# SoC_Decoupling.net
KiCad netlist of a schematic drawn in Altium Designer
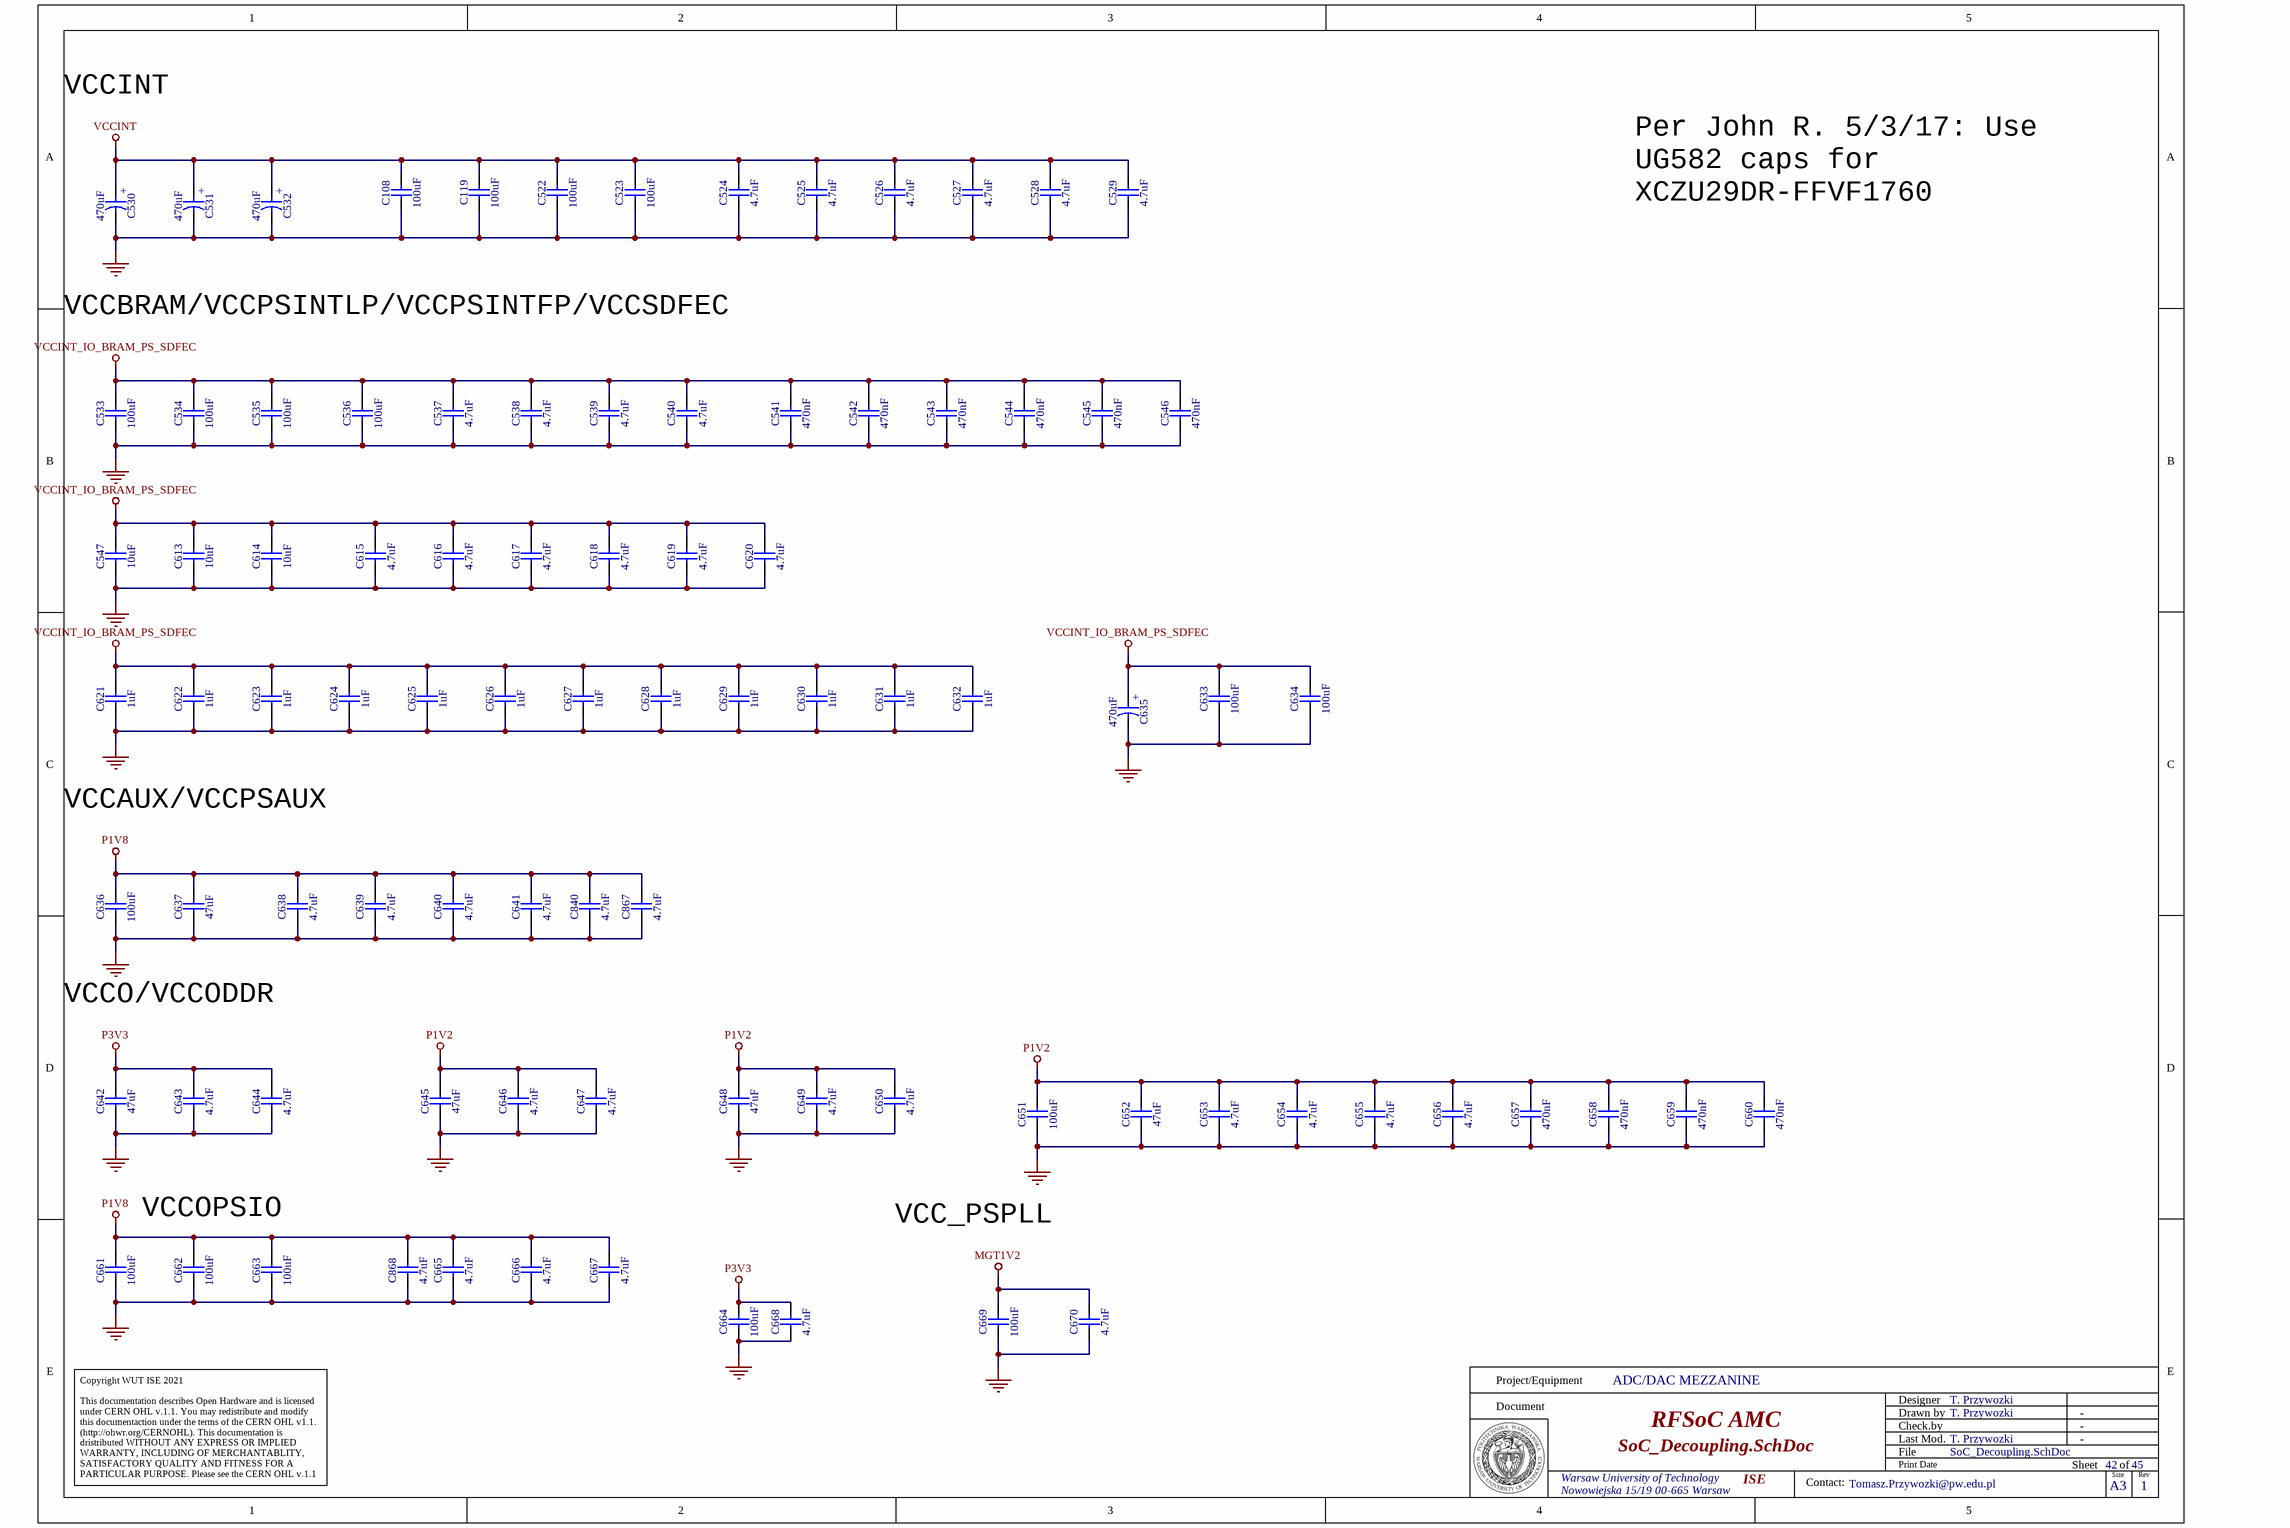
[diagram p0: SoC_Decoupling.SchDoc]

(export (version "E")
  (design (tool "Eeschema 10.0.6"))
  (components
    (comp (ref "C108")
      (value "100uF")
      (footprint "CAPC3216X180N")
      (description "Non-polarised capacitor")
      (fields
        (field (name "VOLTAGE") "6.3V")
        (field (name "TOLERANCE") "±10%")
        (field (name "AUTHOR") "CERN DEM JLC")
      )
      (libsource (lib "Capacitors") (part "Capacitor - non polarized"))
    )
    (comp (ref "C119")
      (value "100uF")
      (footprint "CAPC3216X180N")
      (description "Non-polarised capacitor")
      (fields
        (field (name "VOLTAGE") "6.3V")
        (field (name "TOLERANCE") "±10%")
        (field (name "AUTHOR") "CERN DEM JLC")
      )
      (libsource (lib "Capacitors") (part "Capacitor - non polarized"))
    )
    (comp (ref "C522")
      (value "100uF")
      (footprint "CAPC3216X180N")
      (description "Non-polarised capacitor")
      (fields
        (field (name "VOLTAGE") "6.3V")
        (field (name "TOLERANCE") "±10%")
        (field (name "AUTHOR") "CERN DEM JLC")
      )
      (libsource (lib "Capacitors") (part "Capacitor - non polarized"))
    )
    (comp (ref "C523")
      (value "100uF")
      (footprint "CAPC3216X180N")
      (description "Non-polarised capacitor")
      (fields
        (field (name "VOLTAGE") "6.3V")
        (field (name "TOLERANCE") "±10%")
        (field (name "AUTHOR") "CERN DEM JLC")
      )
      (libsource (lib "Capacitors") (part "Capacitor - non polarized"))
    )
    (comp (ref "C524")
      (value "4.7uF")
      (footprint "CAPC1005X55N")
      (description "Non-polarised capacitor")
      (fields
        (field (name "VOLTAGE") "6.3V")
        (field (name "TOLERANCE") "±20%")
        (field (name "AUTHOR") "CERN DEM JLC")
      )
      (libsource (lib "Capacitors") (part "Capacitor - non polarized"))
    )
    (comp (ref "C525")
      (value "4.7uF")
      (footprint "CAPC1005X55N")
      (description "Non-polarised capacitor")
      (fields
        (field (name "VOLTAGE") "6.3V")
        (field (name "TOLERANCE") "±20%")
        (field (name "AUTHOR") "CERN DEM JLC")
      )
      (libsource (lib "Capacitors") (part "Capacitor - non polarized"))
    )
    (comp (ref "C526")
      (value "4.7uF")
      (footprint "CAPC1005X55N")
      (description "Non-polarised capacitor")
      (fields
        (field (name "VOLTAGE") "6.3V")
        (field (name "TOLERANCE") "±20%")
        (field (name "AUTHOR") "CERN DEM JLC")
      )
      (libsource (lib "Capacitors") (part "Capacitor - non polarized"))
    )
    (comp (ref "C527")
      (value "4.7uF")
      (footprint "CAPC1005X55N")
      (description "Non-polarised capacitor")
      (fields
        (field (name "VOLTAGE") "6.3V")
        (field (name "TOLERANCE") "±20%")
        (field (name "AUTHOR") "CERN DEM JLC")
      )
      (libsource (lib "Capacitors") (part "Capacitor - non polarized"))
    )
    (comp (ref "C528")
      (value "4.7uF")
      (footprint "CAPC1005X55N")
      (description "Non-polarised capacitor")
      (fields
        (field (name "VOLTAGE") "6.3V")
        (field (name "TOLERANCE") "±20%")
        (field (name "AUTHOR") "CERN DEM JLC")
      )
      (libsource (lib "Capacitors") (part "Capacitor - non polarized"))
    )
    (comp (ref "C529")
      (value "4.7uF")
      (footprint "CAPC1005X55N")
      (description "Non-polarised capacitor")
      (fields
        (field (name "VOLTAGE") "6.3V")
        (field (name "TOLERANCE") "±20%")
        (field (name "AUTHOR") "CERN DEM JLC")
      )
      (libsource (lib "Capacitors") (part "Capacitor - non polarized"))
    )
    (comp (ref "C530")
      (value "470uF")
      (footprint "CAPMP7343X200N")
      (description "Polarised capacitor")
      (fields
        (field (name "VOLTAGE") "2V")
        (field (name "TOLERANCE") "±20%")
        (field (name "AUTHOR") "CERN DEM MR")
      )
      (libsource (lib "Capacitors") (part "Capacitor - polarized"))
    )
    (comp (ref "C531")
      (value "470uF")
      (footprint "CAPMP7343X200N")
      (description "Polarised capacitor")
      (fields
        (field (name "VOLTAGE") "2V")
        (field (name "TOLERANCE") "±20%")
        (field (name "AUTHOR") "CERN DEM MR")
      )
      (libsource (lib "Capacitors") (part "Capacitor - polarized"))
    )
    (comp (ref "C532")
      (value "470uF")
      (footprint "CAPMP7343X200N")
      (description "Polarised capacitor")
      (fields
        (field (name "VOLTAGE") "2V")
        (field (name "TOLERANCE") "±20%")
        (field (name "AUTHOR") "CERN DEM MR")
      )
      (libsource (lib "Capacitors") (part "Capacitor - polarized"))
    )
    (comp (ref "C533")
      (value "100uF")
      (footprint "CAPC3225X270N")
      (description "Non-polarised capacitor")
      (fields
        (field (name "VOLTAGE") "6.3V")
        (field (name "TOLERANCE") "±20%")
        (field (name "AUTHOR") "CERN DEM JLC")
      )
      (libsource (lib "Capacitors") (part "Capacitor - non polarized"))
    )
    (comp (ref "C534")
      (value "100uF")
      (footprint "CAPC3225X270N")
      (description "Non-polarised capacitor")
      (fields
        (field (name "VOLTAGE") "6.3V")
        (field (name "TOLERANCE") "±20%")
        (field (name "AUTHOR") "CERN DEM JLC")
      )
      (libsource (lib "Capacitors") (part "Capacitor - non polarized"))
    )
    (comp (ref "C535")
      (value "100uF")
      (footprint "CAPC3225X270N")
      (description "Non-polarised capacitor")
      (fields
        (field (name "VOLTAGE") "6.3V")
        (field (name "TOLERANCE") "±20%")
        (field (name "AUTHOR") "CERN DEM JLC")
      )
      (libsource (lib "Capacitors") (part "Capacitor - non polarized"))
    )
    (comp (ref "C536")
      (value "100uF")
      (footprint "CAPC3225X270N")
      (description "Non-polarised capacitor")
      (fields
        (field (name "VOLTAGE") "6.3V")
        (field (name "TOLERANCE") "±20%")
        (field (name "AUTHOR") "CERN DEM JLC")
      )
      (libsource (lib "Capacitors") (part "Capacitor - non polarized"))
    )
    (comp (ref "C537")
      (value "4.7uF")
      (footprint "CAPC1005X55N")
      (description "Non-polarised capacitor")
      (fields
        (field (name "VOLTAGE") "6.3V")
        (field (name "TOLERANCE") "±20%")
        (field (name "AUTHOR") "CERN DEM JLC")
      )
      (libsource (lib "Capacitors") (part "Capacitor - non polarized"))
    )
    (comp (ref "C538")
      (value "4.7uF")
      (footprint "CAPC1005X55N")
      (description "Non-polarised capacitor")
      (fields
        (field (name "VOLTAGE") "6.3V")
        (field (name "TOLERANCE") "±20%")
        (field (name "AUTHOR") "CERN DEM JLC")
      )
      (libsource (lib "Capacitors") (part "Capacitor - non polarized"))
    )
    (comp (ref "C539")
      (value "4.7uF")
      (footprint "CAPC1005X55N")
      (description "Non-polarised capacitor")
      (fields
        (field (name "VOLTAGE") "6.3V")
        (field (name "TOLERANCE") "±20%")
        (field (name "AUTHOR") "CERN DEM JLC")
      )
      (libsource (lib "Capacitors") (part "Capacitor - non polarized"))
    )
    (comp (ref "C540")
      (value "4.7uF")
      (footprint "CAPC1005X55N")
      (description "Non-polarised capacitor")
      (fields
        (field (name "VOLTAGE") "6.3V")
        (field (name "TOLERANCE") "±20%")
        (field (name "AUTHOR") "CERN DEM JLC")
      )
      (libsource (lib "Capacitors") (part "Capacitor - non polarized"))
    )
    (comp (ref "C541")
      (value "470nF")
      (footprint "CAPC1005X55N")
      (description "Non-polarised capacitor")
      (fields
        (field (name "VOLTAGE") "16V")
        (field (name "TOLERANCE") "±10%")
        (field (name "AUTHOR") "CERN DEM JLC")
      )
      (libsource (lib "Capacitors") (part "Capacitor - non polarized"))
    )
    (comp (ref "C542")
      (value "470nF")
      (footprint "CAPC1005X55N")
      (description "Non-polarised capacitor")
      (fields
        (field (name "VOLTAGE") "16V")
        (field (name "TOLERANCE") "±10%")
        (field (name "AUTHOR") "CERN DEM JLC")
      )
      (libsource (lib "Capacitors") (part "Capacitor - non polarized"))
    )
    (comp (ref "C543")
      (value "470nF")
      (footprint "CAPC1005X55N")
      (description "Non-polarised capacitor")
      (fields
        (field (name "VOLTAGE") "16V")
        (field (name "TOLERANCE") "±10%")
        (field (name "AUTHOR") "CERN DEM JLC")
      )
      (libsource (lib "Capacitors") (part "Capacitor - non polarized"))
    )
    (comp (ref "C544")
      (value "470nF")
      (footprint "CAPC1005X55N")
      (description "Non-polarised capacitor")
      (fields
        (field (name "VOLTAGE") "16V")
        (field (name "TOLERANCE") "±10%")
        (field (name "AUTHOR") "CERN DEM JLC")
      )
      (libsource (lib "Capacitors") (part "Capacitor - non polarized"))
    )
    (comp (ref "C545")
      (value "470nF")
      (footprint "CAPC1005X55N")
      (description "Non-polarised capacitor")
      (fields
        (field (name "VOLTAGE") "16V")
        (field (name "TOLERANCE") "±10%")
        (field (name "AUTHOR") "CERN DEM JLC")
      )
      (libsource (lib "Capacitors") (part "Capacitor - non polarized"))
    )
    (comp (ref "C546")
      (value "470nF")
      (footprint "CAPC1005X55N")
      (description "Non-polarised capacitor")
      (fields
        (field (name "VOLTAGE") "16V")
        (field (name "TOLERANCE") "±10%")
        (field (name "AUTHOR") "CERN DEM JLC")
      )
      (libsource (lib "Capacitors") (part "Capacitor - non polarized"))
    )
    (comp (ref "C547")
      (value "10uF")
      (footprint "CAPC1608X80N")
      (description "Non-polarised capacitor")
      (fields
        (field (name "VOLTAGE") "10V")
        (field (name "TOLERANCE") "±10%")
        (field (name "AUTHOR") "CERN DEM JLC")
      )
      (libsource (lib "Capacitors") (part "Capacitor - non polarized"))
    )
    (comp (ref "C613")
      (value "10uF")
      (footprint "CAPC1608X80N")
      (description "Non-polarised capacitor")
      (fields
        (field (name "VOLTAGE") "10V")
        (field (name "TOLERANCE") "±10%")
        (field (name "AUTHOR") "CERN DEM JLC")
      )
      (libsource (lib "Capacitors") (part "Capacitor - non polarized"))
    )
    (comp (ref "C614")
      (value "10uF")
      (footprint "CAPC1608X80N")
      (description "Non-polarised capacitor")
      (fields
        (field (name "VOLTAGE") "10V")
        (field (name "TOLERANCE") "±10%")
        (field (name "AUTHOR") "CERN DEM JLC")
      )
      (libsource (lib "Capacitors") (part "Capacitor - non polarized"))
    )
    (comp (ref "C615")
      (value "4.7uF")
      (footprint "CAPC1005X55N")
      (description "Non-polarised capacitor")
      (fields
        (field (name "VOLTAGE") "6.3V")
        (field (name "TOLERANCE") "±20%")
        (field (name "AUTHOR") "CERN DEM JLC")
      )
      (libsource (lib "Capacitors") (part "Capacitor - non polarized"))
    )
    (comp (ref "C616")
      (value "4.7uF")
      (footprint "CAPC1005X55N")
      (description "Non-polarised capacitor")
      (fields
        (field (name "VOLTAGE") "6.3V")
        (field (name "TOLERANCE") "±20%")
        (field (name "AUTHOR") "CERN DEM JLC")
      )
      (libsource (lib "Capacitors") (part "Capacitor - non polarized"))
    )
    (comp (ref "C617")
      (value "4.7uF")
      (footprint "CAPC1005X55N")
      (description "Non-polarised capacitor")
      (fields
        (field (name "VOLTAGE") "6.3V")
        (field (name "TOLERANCE") "±20%")
        (field (name "AUTHOR") "CERN DEM JLC")
      )
      (libsource (lib "Capacitors") (part "Capacitor - non polarized"))
    )
    (comp (ref "C618")
      (value "4.7uF")
      (footprint "CAPC1005X55N")
      (description "Non-polarised capacitor")
      (fields
        (field (name "VOLTAGE") "6.3V")
        (field (name "TOLERANCE") "±20%")
        (field (name "AUTHOR") "CERN DEM JLC")
      )
      (libsource (lib "Capacitors") (part "Capacitor - non polarized"))
    )
    (comp (ref "C619")
      (value "4.7uF")
      (footprint "CAPC1005X55N")
      (description "Non-polarised capacitor")
      (fields
        (field (name "VOLTAGE") "6.3V")
        (field (name "TOLERANCE") "±20%")
        (field (name "AUTHOR") "CERN DEM JLC")
      )
      (libsource (lib "Capacitors") (part "Capacitor - non polarized"))
    )
    (comp (ref "C620")
      (value "4.7uF")
      (footprint "CAPC1005X55N")
      (description "Non-polarised capacitor")
      (fields
        (field (name "VOLTAGE") "6.3V")
        (field (name "TOLERANCE") "±20%")
        (field (name "AUTHOR") "CERN DEM JLC")
      )
      (libsource (lib "Capacitors") (part "Capacitor - non polarized"))
    )
    (comp (ref "C621")
      (value "1uF")
      (footprint "CAPC1005X55N")
      (description "Non-polarised capacitor")
      (fields
        (field (name "VOLTAGE") "16V")
        (field (name "TOLERANCE") "±10%")
        (field (name "AUTHOR") "CERN DEM JLC")
      )
      (libsource (lib "Capacitors") (part "Capacitor - non polarized"))
    )
    (comp (ref "C622")
      (value "1uF")
      (footprint "CAPC1005X55N")
      (description "Non-polarised capacitor")
      (fields
        (field (name "VOLTAGE") "16V")
        (field (name "TOLERANCE") "±10%")
        (field (name "AUTHOR") "CERN DEM JLC")
      )
      (libsource (lib "Capacitors") (part "Capacitor - non polarized"))
    )
    (comp (ref "C623")
      (value "1uF")
      (footprint "CAPC1005X55N")
      (description "Non-polarised capacitor")
      (fields
        (field (name "VOLTAGE") "16V")
        (field (name "TOLERANCE") "±10%")
        (field (name "AUTHOR") "CERN DEM JLC")
      )
      (libsource (lib "Capacitors") (part "Capacitor - non polarized"))
    )
    (comp (ref "C624")
      (value "1uF")
      (footprint "CAPC1005X55N")
      (description "Non-polarised capacitor")
      (fields
        (field (name "VOLTAGE") "16V")
        (field (name "TOLERANCE") "±10%")
        (field (name "AUTHOR") "CERN DEM JLC")
      )
      (libsource (lib "Capacitors") (part "Capacitor - non polarized"))
    )
    (comp (ref "C625")
      (value "1uF")
      (footprint "CAPC1005X55N")
      (description "Non-polarised capacitor")
      (fields
        (field (name "VOLTAGE") "16V")
        (field (name "TOLERANCE") "±10%")
        (field (name "AUTHOR") "CERN DEM JLC")
      )
      (libsource (lib "Capacitors") (part "Capacitor - non polarized"))
    )
    (comp (ref "C626")
      (value "1uF")
      (footprint "CAPC1005X55N")
      (description "Non-polarised capacitor")
      (fields
        (field (name "VOLTAGE") "16V")
        (field (name "TOLERANCE") "±10%")
        (field (name "AUTHOR") "CERN DEM JLC")
      )
      (libsource (lib "Capacitors") (part "Capacitor - non polarized"))
    )
    (comp (ref "C627")
      (value "1uF")
      (footprint "CAPC1005X55N")
      (description "Non-polarised capacitor")
      (fields
        (field (name "VOLTAGE") "16V")
        (field (name "TOLERANCE") "±10%")
        (field (name "AUTHOR") "CERN DEM JLC")
      )
      (libsource (lib "Capacitors") (part "Capacitor - non polarized"))
    )
    (comp (ref "C628")
      (value "1uF")
      (footprint "CAPC1005X55N")
      (description "Non-polarised capacitor")
      (fields
        (field (name "VOLTAGE") "16V")
        (field (name "TOLERANCE") "±10%")
        (field (name "AUTHOR") "CERN DEM JLC")
      )
      (libsource (lib "Capacitors") (part "Capacitor - non polarized"))
    )
    (comp (ref "C629")
      (value "1uF")
      (footprint "CAPC1005X55N")
      (description "Non-polarised capacitor")
      (fields
        (field (name "VOLTAGE") "16V")
        (field (name "TOLERANCE") "±10%")
        (field (name "AUTHOR") "CERN DEM JLC")
      )
      (libsource (lib "Capacitors") (part "Capacitor - non polarized"))
    )
    (comp (ref "C630")
      (value "1uF")
      (footprint "CAPC1005X55N")
      (description "Non-polarised capacitor")
      (fields
        (field (name "VOLTAGE") "16V")
        (field (name "TOLERANCE") "±10%")
        (field (name "AUTHOR") "CERN DEM JLC")
      )
      (libsource (lib "Capacitors") (part "Capacitor - non polarized"))
    )
    (comp (ref "C631")
      (value "1uF")
      (footprint "CAPC1005X55N")
      (description "Non-polarised capacitor")
      (fields
        (field (name "VOLTAGE") "16V")
        (field (name "TOLERANCE") "±10%")
        (field (name "AUTHOR") "CERN DEM JLC")
      )
      (libsource (lib "Capacitors") (part "Capacitor - non polarized"))
    )
    (comp (ref "C632")
      (value "1uF")
      (footprint "CAPC1005X55N")
      (description "Non-polarised capacitor")
      (fields
        (field (name "VOLTAGE") "16V")
        (field (name "TOLERANCE") "±10%")
        (field (name "AUTHOR") "CERN DEM JLC")
      )
      (libsource (lib "Capacitors") (part "Capacitor - non polarized"))
    )
    (comp (ref "C633")
      (value "100uF")
      (footprint "CAPC3225X270N")
      (description "Non-polarised capacitor")
      (fields
        (field (name "VOLTAGE") "6.3V")
        (field (name "TOLERANCE") "±20%")
        (field (name "AUTHOR") "CERN DEM JLC")
      )
      (libsource (lib "Capacitors") (part "Capacitor - non polarized"))
    )
    (comp (ref "C634")
      (value "100uF")
      (footprint "CAPC3225X270N")
      (description "Non-polarised capacitor")
      (fields
        (field (name "VOLTAGE") "6.3V")
        (field (name "TOLERANCE") "±20%")
        (field (name "AUTHOR") "CERN DEM JLC")
      )
      (libsource (lib "Capacitors") (part "Capacitor - non polarized"))
    )
    (comp (ref "C635")
      (value "470uF")
      (footprint "CAPMP7343X200N")
      (description "Polarised capacitor")
      (fields
        (field (name "VOLTAGE") "2V")
        (field (name "TOLERANCE") "±20%")
        (field (name "AUTHOR") "CERN DEM MR")
      )
      (libsource (lib "Capacitors") (part "Capacitor - polarized"))
    )
    (comp (ref "C636")
      (value "100uF")
      (footprint "CAPC3225X270N")
      (description "Non-polarised capacitor")
      (fields
        (field (name "VOLTAGE") "6.3V")
        (field (name "TOLERANCE") "±20%")
        (field (name "AUTHOR") "CERN DEM JLC")
      )
      (libsource (lib "Capacitors") (part "Capacitor - non polarized"))
    )
    (comp (ref "C637")
      (value "47uF")
      (footprint "CAPC1608X100N")
      (description "Non-polarised capacitor")
      (fields
        (field (name "VOLTAGE") "6.3V")
        (field (name "TOLERANCE") "±20%")
        (field (name "AUTHOR") "CERN DEM JLC")
      )
      (libsource (lib "Capacitors") (part "Capacitor - non polarized"))
    )
    (comp (ref "C638")
      (value "4.7uF")
      (footprint "CAPC1005X55N")
      (description "Non-polarised capacitor")
      (fields
        (field (name "VOLTAGE") "6.3V")
        (field (name "TOLERANCE") "±20%")
        (field (name "AUTHOR") "CERN DEM JLC")
      )
      (libsource (lib "Capacitors") (part "Capacitor - non polarized"))
    )
    (comp (ref "C639")
      (value "4.7uF")
      (footprint "CAPC1005X55N")
      (description "Non-polarised capacitor")
      (fields
        (field (name "VOLTAGE") "6.3V")
        (field (name "TOLERANCE") "±20%")
        (field (name "AUTHOR") "CERN DEM JLC")
      )
      (libsource (lib "Capacitors") (part "Capacitor - non polarized"))
    )
    (comp (ref "C640")
      (value "4.7uF")
      (footprint "CAPC1005X55N")
      (description "Non-polarised capacitor")
      (fields
        (field (name "VOLTAGE") "6.3V")
        (field (name "TOLERANCE") "±20%")
        (field (name "AUTHOR") "CERN DEM JLC")
      )
      (libsource (lib "Capacitors") (part "Capacitor - non polarized"))
    )
    (comp (ref "C641")
      (value "4.7uF")
      (footprint "CAPC1005X55N")
      (description "Non-polarised capacitor")
      (fields
        (field (name "VOLTAGE") "6.3V")
        (field (name "TOLERANCE") "±20%")
        (field (name "AUTHOR") "CERN DEM JLC")
      )
      (libsource (lib "Capacitors") (part "Capacitor - non polarized"))
    )
    (comp (ref "C642")
      (value "47uF")
      (footprint "CAPC1608X100N")
      (description "Non-polarised capacitor")
      (fields
        (field (name "VOLTAGE") "6.3V")
        (field (name "TOLERANCE") "±20%")
        (field (name "AUTHOR") "CERN DEM JLC")
      )
      (libsource (lib "Capacitors") (part "Capacitor - non polarized"))
    )
    (comp (ref "C643")
      (value "4.7uF")
      (footprint "CAPC1005X55N")
      (description "Non-polarised capacitor")
      (fields
        (field (name "VOLTAGE") "6.3V")
        (field (name "TOLERANCE") "±20%")
        (field (name "AUTHOR") "CERN DEM JLC")
      )
      (libsource (lib "Capacitors") (part "Capacitor - non polarized"))
    )
    (comp (ref "C644")
      (value "4.7uF")
      (footprint "CAPC1005X55N")
      (description "Non-polarised capacitor")
      (fields
        (field (name "VOLTAGE") "6.3V")
        (field (name "TOLERANCE") "±20%")
        (field (name "AUTHOR") "CERN DEM JLC")
      )
      (libsource (lib "Capacitors") (part "Capacitor - non polarized"))
    )
    (comp (ref "C645")
      (value "47uF")
      (footprint "CAPC1608X100N")
      (description "Non-polarised capacitor")
      (fields
        (field (name "VOLTAGE") "6.3V")
        (field (name "TOLERANCE") "±20%")
        (field (name "AUTHOR") "CERN DEM JLC")
      )
      (libsource (lib "Capacitors") (part "Capacitor - non polarized"))
    )
    (comp (ref "C646")
      (value "4.7uF")
      (footprint "CAPC1005X55N")
      (description "Non-polarised capacitor")
      (fields
        (field (name "VOLTAGE") "6.3V")
        (field (name "TOLERANCE") "±20%")
        (field (name "AUTHOR") "CERN DEM JLC")
      )
      (libsource (lib "Capacitors") (part "Capacitor - non polarized"))
    )
    (comp (ref "C647")
      (value "4.7uF")
      (footprint "CAPC1005X55N")
      (description "Non-polarised capacitor")
      (fields
        (field (name "VOLTAGE") "6.3V")
        (field (name "TOLERANCE") "±20%")
        (field (name "AUTHOR") "CERN DEM JLC")
      )
      (libsource (lib "Capacitors") (part "Capacitor - non polarized"))
    )
    (comp (ref "C648")
      (value "47uF")
      (footprint "CAPC1608X100N")
      (description "Non-polarised capacitor")
      (fields
        (field (name "VOLTAGE") "6.3V")
        (field (name "TOLERANCE") "±20%")
        (field (name "AUTHOR") "CERN DEM JLC")
      )
      (libsource (lib "Capacitors") (part "Capacitor - non polarized"))
    )
    (comp (ref "C649")
      (value "4.7uF")
      (footprint "CAPC1005X55N")
      (description "Non-polarised capacitor")
      (fields
        (field (name "VOLTAGE") "6.3V")
        (field (name "TOLERANCE") "±20%")
        (field (name "AUTHOR") "CERN DEM JLC")
      )
      (libsource (lib "Capacitors") (part "Capacitor - non polarized"))
    )
    (comp (ref "C650")
      (value "4.7uF")
      (footprint "CAPC1005X55N")
      (description "Non-polarised capacitor")
      (fields
        (field (name "VOLTAGE") "6.3V")
        (field (name "TOLERANCE") "±20%")
        (field (name "AUTHOR") "CERN DEM JLC")
      )
      (libsource (lib "Capacitors") (part "Capacitor - non polarized"))
    )
    (comp (ref "C651")
      (value "100uF")
      (footprint "CAPC3225X270N")
      (description "Non-polarised capacitor")
      (fields
        (field (name "VOLTAGE") "6.3V")
        (field (name "TOLERANCE") "±20%")
        (field (name "AUTHOR") "CERN DEM JLC")
      )
      (libsource (lib "Capacitors") (part "Capacitor - non polarized"))
    )
    (comp (ref "C652")
      (value "47uF")
      (footprint "CAPC1608X100N")
      (description "Non-polarised capacitor")
      (fields
        (field (name "VOLTAGE") "6.3V")
        (field (name "TOLERANCE") "±20%")
        (field (name "AUTHOR") "CERN DEM JLC")
      )
      (libsource (lib "Capacitors") (part "Capacitor - non polarized"))
    )
    (comp (ref "C653")
      (value "4.7uF")
      (footprint "CAPC1005X55N")
      (description "Non-polarised capacitor")
      (fields
        (field (name "VOLTAGE") "6.3V")
        (field (name "TOLERANCE") "±20%")
        (field (name "AUTHOR") "CERN DEM JLC")
      )
      (libsource (lib "Capacitors") (part "Capacitor - non polarized"))
    )
    (comp (ref "C654")
      (value "4.7uF")
      (footprint "CAPC1005X55N")
      (description "Non-polarised capacitor")
      (fields
        (field (name "VOLTAGE") "6.3V")
        (field (name "TOLERANCE") "±20%")
        (field (name "AUTHOR") "CERN DEM JLC")
      )
      (libsource (lib "Capacitors") (part "Capacitor - non polarized"))
    )
    (comp (ref "C655")
      (value "4.7uF")
      (footprint "CAPC1005X55N")
      (description "Non-polarised capacitor")
      (fields
        (field (name "VOLTAGE") "6.3V")
        (field (name "TOLERANCE") "±20%")
        (field (name "AUTHOR") "CERN DEM JLC")
      )
      (libsource (lib "Capacitors") (part "Capacitor - non polarized"))
    )
    (comp (ref "C656")
      (value "4.7uF")
      (footprint "CAPC1005X55N")
      (description "Non-polarised capacitor")
      (fields
        (field (name "VOLTAGE") "6.3V")
        (field (name "TOLERANCE") "±20%")
        (field (name "AUTHOR") "CERN DEM JLC")
      )
      (libsource (lib "Capacitors") (part "Capacitor - non polarized"))
    )
    (comp (ref "C657")
      (value "470nF")
      (footprint "CAPC1005X55N")
      (description "Non-polarised capacitor")
      (fields
        (field (name "VOLTAGE") "16V")
        (field (name "TOLERANCE") "±10%")
        (field (name "AUTHOR") "CERN DEM JLC")
      )
      (libsource (lib "Capacitors") (part "Capacitor - non polarized"))
    )
    (comp (ref "C658")
      (value "470nF")
      (footprint "CAPC1005X55N")
      (description "Non-polarised capacitor")
      (fields
        (field (name "VOLTAGE") "16V")
        (field (name "TOLERANCE") "±10%")
        (field (name "AUTHOR") "CERN DEM JLC")
      )
      (libsource (lib "Capacitors") (part "Capacitor - non polarized"))
    )
    (comp (ref "C659")
      (value "470nF")
      (footprint "CAPC1005X55N")
      (description "Non-polarised capacitor")
      (fields
        (field (name "VOLTAGE") "16V")
        (field (name "TOLERANCE") "±10%")
        (field (name "AUTHOR") "CERN DEM JLC")
      )
      (libsource (lib "Capacitors") (part "Capacitor - non polarized"))
    )
    (comp (ref "C660")
      (value "470nF")
      (footprint "CAPC1005X55N")
      (description "Non-polarised capacitor")
      (fields
        (field (name "VOLTAGE") "16V")
        (field (name "TOLERANCE") "±10%")
        (field (name "AUTHOR") "CERN DEM JLC")
      )
      (libsource (lib "Capacitors") (part "Capacitor - non polarized"))
    )
    (comp (ref "C661")
      (value "100uF")
      (footprint "CAPC3225X270N")
      (description "Non-polarised capacitor")
      (fields
        (field (name "VOLTAGE") "6.3V")
        (field (name "TOLERANCE") "±20%")
        (field (name "AUTHOR") "CERN DEM JLC")
      )
      (libsource (lib "Capacitors") (part "Capacitor - non polarized"))
    )
    (comp (ref "C662")
      (value "100uF")
      (footprint "CAPC3225X270N")
      (description "Non-polarised capacitor")
      (fields
        (field (name "VOLTAGE") "6.3V")
        (field (name "TOLERANCE") "±20%")
        (field (name "AUTHOR") "CERN DEM JLC")
      )
      (libsource (lib "Capacitors") (part "Capacitor - non polarized"))
    )
    (comp (ref "C663")
      (value "100uF")
      (footprint "CAPC3225X270N")
      (description "Non-polarised capacitor")
      (fields
        (field (name "VOLTAGE") "6.3V")
        (field (name "TOLERANCE") "±20%")
        (field (name "AUTHOR") "CERN DEM JLC")
      )
      (libsource (lib "Capacitors") (part "Capacitor - non polarized"))
    )
    (comp (ref "C664")
      (value "100uF")
      (footprint "CAPC3225X270N")
      (description "Non-polarised capacitor")
      (fields
        (field (name "VOLTAGE") "6.3V")
        (field (name "TOLERANCE") "±20%")
        (field (name "AUTHOR") "CERN DEM JLC")
      )
      (libsource (lib "Capacitors") (part "Capacitor - non polarized"))
    )
    (comp (ref "C665")
      (value "4.7uF")
      (footprint "CAPC1005X55N")
      (description "Non-polarised capacitor")
      (fields
        (field (name "VOLTAGE") "6.3V")
        (field (name "TOLERANCE") "±20%")
        (field (name "AUTHOR") "CERN DEM JLC")
      )
      (libsource (lib "Capacitors") (part "Capacitor - non polarized"))
    )
    (comp (ref "C666")
      (value "4.7uF")
      (footprint "CAPC1005X55N")
      (description "Non-polarised capacitor")
      (fields
        (field (name "VOLTAGE") "6.3V")
        (field (name "TOLERANCE") "±20%")
        (field (name "AUTHOR") "CERN DEM JLC")
      )
      (libsource (lib "Capacitors") (part "Capacitor - non polarized"))
    )
    (comp (ref "C667")
      (value "4.7uF")
      (footprint "CAPC1005X55N")
      (description "Non-polarised capacitor")
      (fields
        (field (name "VOLTAGE") "6.3V")
        (field (name "TOLERANCE") "±20%")
        (field (name "AUTHOR") "CERN DEM JLC")
      )
      (libsource (lib "Capacitors") (part "Capacitor - non polarized"))
    )
    (comp (ref "C668")
      (value "4.7uF")
      (footprint "CAPC1005X55N")
      (description "Non-polarised capacitor")
      (fields
        (field (name "VOLTAGE") "6.3V")
        (field (name "TOLERANCE") "±20%")
        (field (name "AUTHOR") "CERN DEM JLC")
      )
      (libsource (lib "Capacitors") (part "Capacitor - non polarized"))
    )
    (comp (ref "C669")
      (value "100uF")
      (footprint "CAPC3216X180N")
      (description "Non-polarised capacitor")
      (fields
        (field (name "VOLTAGE") "6.3V")
        (field (name "TOLERANCE") "±10%")
        (field (name "AUTHOR") "CERN DEM JLC")
      )
      (libsource (lib "Capacitors") (part "Capacitor - non polarized"))
    )
    (comp (ref "C670")
      (value "4.7uF")
      (footprint "CAPC1005X55N")
      (description "Non-polarised capacitor")
      (fields
        (field (name "VOLTAGE") "6.3V")
        (field (name "TOLERANCE") "±20%")
        (field (name "AUTHOR") "CERN DEM JLC")
      )
      (libsource (lib "Capacitors") (part "Capacitor - non polarized"))
    )
    (comp (ref "C840")
      (value "4.7uF")
      (footprint "CAPC1005X55N")
      (description "Non-polarised capacitor")
      (fields
        (field (name "VOLTAGE") "6.3V")
        (field (name "TOLERANCE") "±20%")
        (field (name "AUTHOR") "CERN DEM JLC")
      )
      (libsource (lib "Capacitors") (part "Capacitor - non polarized"))
    )
    (comp (ref "C867")
      (value "4.7uF")
      (footprint "CAPC1005X55N")
      (description "Non-polarised capacitor")
      (fields
        (field (name "VOLTAGE") "6.3V")
        (field (name "TOLERANCE") "±20%")
        (field (name "AUTHOR") "CERN DEM JLC")
      )
      (libsource (lib "Capacitors") (part "Capacitor - non polarized"))
    )
    (comp (ref "C868")
      (value "4.7uF")
      (footprint "CAPC1005X55N")
      (description "Non-polarised capacitor")
      (fields
        (field (name "VOLTAGE") "6.3V")
        (field (name "TOLERANCE") "±20%")
        (field (name "AUTHOR") "CERN DEM JLC")
      )
      (libsource (lib "Capacitors") (part "Capacitor - non polarized"))
    )
  )
  (nets
    (net (code "1") (name "GND") (class "Default")
      (node (ref "C108") (pin "1") (pinfunction "1_1") (pintype "passive"))
      (node (ref "C119") (pin "1") (pinfunction "1_1") (pintype "passive"))
      (node (ref "C522") (pin "1") (pinfunction "1_1") (pintype "passive"))
      (node (ref "C523") (pin "1") (pinfunction "1_1") (pintype "passive"))
      (node (ref "C524") (pin "1") (pinfunction "1_1") (pintype "passive"))
      (node (ref "C525") (pin "1") (pinfunction "1_1") (pintype "passive"))
      (node (ref "C526") (pin "1") (pinfunction "1_1") (pintype "passive"))
      (node (ref "C527") (pin "1") (pinfunction "1_1") (pintype "passive"))
      (node (ref "C528") (pin "1") (pinfunction "1_1") (pintype "passive"))
      (node (ref "C529") (pin "1") (pinfunction "1_1") (pintype "passive"))
      (node (ref "C530") (pin "2") (pinfunction "2_2") (pintype "passive"))
      (node (ref "C531") (pin "2") (pinfunction "2_2") (pintype "passive"))
      (node (ref "C532") (pin "2") (pinfunction "2_2") (pintype "passive"))
      (node (ref "C533") (pin "1") (pinfunction "1_1") (pintype "passive"))
      (node (ref "C534") (pin "1") (pinfunction "1_1") (pintype "passive"))
      (node (ref "C535") (pin "1") (pinfunction "1_1") (pintype "passive"))
      (node (ref "C536") (pin "1") (pinfunction "1_1") (pintype "passive"))
      (node (ref "C537") (pin "1") (pinfunction "1_1") (pintype "passive"))
      (node (ref "C538") (pin "1") (pinfunction "1_1") (pintype "passive"))
      (node (ref "C539") (pin "1") (pinfunction "1_1") (pintype "passive"))
      (node (ref "C540") (pin "1") (pinfunction "1_1") (pintype "passive"))
      (node (ref "C541") (pin "1") (pinfunction "1_1") (pintype "passive"))
      (node (ref "C542") (pin "1") (pinfunction "1_1") (pintype "passive"))
      (node (ref "C543") (pin "1") (pinfunction "1_1") (pintype "passive"))
      (node (ref "C544") (pin "1") (pinfunction "1_1") (pintype "passive"))
      (node (ref "C545") (pin "1") (pinfunction "1_1") (pintype "passive"))
      (node (ref "C546") (pin "1") (pinfunction "1_1") (pintype "passive"))
      (node (ref "C547") (pin "1") (pinfunction "1_1") (pintype "passive"))
      (node (ref "C613") (pin "1") (pinfunction "1_1") (pintype "passive"))
      (node (ref "C614") (pin "1") (pinfunction "1_1") (pintype "passive"))
      (node (ref "C615") (pin "1") (pinfunction "1_1") (pintype "passive"))
      (node (ref "C616") (pin "1") (pinfunction "1_1") (pintype "passive"))
      (node (ref "C617") (pin "1") (pinfunction "1_1") (pintype "passive"))
      (node (ref "C618") (pin "1") (pinfunction "1_1") (pintype "passive"))
      (node (ref "C619") (pin "1") (pinfunction "1_1") (pintype "passive"))
      (node (ref "C620") (pin "1") (pinfunction "1_1") (pintype "passive"))
      (node (ref "C621") (pin "1") (pinfunction "1_1") (pintype "passive"))
      (node (ref "C622") (pin "1") (pinfunction "1_1") (pintype "passive"))
      (node (ref "C623") (pin "1") (pinfunction "1_1") (pintype "passive"))
      (node (ref "C624") (pin "1") (pinfunction "1_1") (pintype "passive"))
      (node (ref "C625") (pin "1") (pinfunction "1_1") (pintype "passive"))
      (node (ref "C626") (pin "1") (pinfunction "1_1") (pintype "passive"))
      (node (ref "C627") (pin "1") (pinfunction "1_1") (pintype "passive"))
      (node (ref "C628") (pin "1") (pinfunction "1_1") (pintype "passive"))
      (node (ref "C629") (pin "1") (pinfunction "1_1") (pintype "passive"))
      (node (ref "C630") (pin "1") (pinfunction "1_1") (pintype "passive"))
      (node (ref "C631") (pin "1") (pinfunction "1_1") (pintype "passive"))
      (node (ref "C632") (pin "1") (pinfunction "1_1") (pintype "passive"))
      (node (ref "C633") (pin "1") (pinfunction "1_1") (pintype "passive"))
      (node (ref "C634") (pin "1") (pinfunction "1_1") (pintype "passive"))
      (node (ref "C635") (pin "2") (pinfunction "2_2") (pintype "passive"))
      (node (ref "C636") (pin "1") (pinfunction "1_1") (pintype "passive"))
      (node (ref "C637") (pin "1") (pinfunction "1_1") (pintype "passive"))
      (node (ref "C638") (pin "1") (pinfunction "1_1") (pintype "passive"))
      (node (ref "C639") (pin "1") (pinfunction "1_1") (pintype "passive"))
      (node (ref "C640") (pin "1") (pinfunction "1_1") (pintype "passive"))
      (node (ref "C641") (pin "1") (pinfunction "1_1") (pintype "passive"))
      (node (ref "C642") (pin "1") (pinfunction "1_1") (pintype "passive"))
      (node (ref "C643") (pin "1") (pinfunction "1_1") (pintype "passive"))
      (node (ref "C644") (pin "1") (pinfunction "1_1") (pintype "passive"))
      (node (ref "C645") (pin "1") (pinfunction "1_1") (pintype "passive"))
      (node (ref "C646") (pin "1") (pinfunction "1_1") (pintype "passive"))
      (node (ref "C647") (pin "1") (pinfunction "1_1") (pintype "passive"))
      (node (ref "C648") (pin "1") (pinfunction "1_1") (pintype "passive"))
      (node (ref "C649") (pin "1") (pinfunction "1_1") (pintype "passive"))
      (node (ref "C650") (pin "1") (pinfunction "1_1") (pintype "passive"))
      (node (ref "C651") (pin "1") (pinfunction "1_1") (pintype "passive"))
      (node (ref "C652") (pin "1") (pinfunction "1_1") (pintype "passive"))
      (node (ref "C653") (pin "1") (pinfunction "1_1") (pintype "passive"))
      (node (ref "C654") (pin "1") (pinfunction "1_1") (pintype "passive"))
      (node (ref "C655") (pin "1") (pinfunction "1_1") (pintype "passive"))
      (node (ref "C656") (pin "1") (pinfunction "1_1") (pintype "passive"))
      (node (ref "C657") (pin "1") (pinfunction "1_1") (pintype "passive"))
      (node (ref "C658") (pin "1") (pinfunction "1_1") (pintype "passive"))
      (node (ref "C659") (pin "1") (pinfunction "1_1") (pintype "passive"))
      (node (ref "C660") (pin "1") (pinfunction "1_1") (pintype "passive"))
      (node (ref "C661") (pin "1") (pinfunction "1_1") (pintype "passive"))
      (node (ref "C662") (pin "1") (pinfunction "1_1") (pintype "passive"))
      (node (ref "C663") (pin "1") (pinfunction "1_1") (pintype "passive"))
      (node (ref "C664") (pin "1") (pinfunction "1_1") (pintype "passive"))
      (node (ref "C665") (pin "1") (pinfunction "1_1") (pintype "passive"))
      (node (ref "C666") (pin "1") (pinfunction "1_1") (pintype "passive"))
      (node (ref "C667") (pin "1") (pinfunction "1_1") (pintype "passive"))
      (node (ref "C668") (pin "1") (pinfunction "1_1") (pintype "passive"))
      (node (ref "C669") (pin "1") (pinfunction "1_1") (pintype "passive"))
      (node (ref "C670") (pin "1") (pinfunction "1_1") (pintype "passive"))
      (node (ref "C840") (pin "1") (pinfunction "1_1") (pintype "passive"))
      (node (ref "C867") (pin "1") (pinfunction "1_1") (pintype "passive"))
      (node (ref "C868") (pin "1") (pinfunction "1_1") (pintype "passive"))
    )
    (net (code "2") (name "MGT1V2") (class "Default")
      (node (ref "C669") (pin "2") (pinfunction "2_2") (pintype "passive"))
      (node (ref "C670") (pin "2") (pinfunction "2_2") (pintype "passive"))
    )
    (net (code "3") (name "P1V2") (class "Default")
      (node (ref "C645") (pin "2") (pinfunction "2_2") (pintype "passive"))
      (node (ref "C646") (pin "2") (pinfunction "2_2") (pintype "passive"))
      (node (ref "C647") (pin "2") (pinfunction "2_2") (pintype "passive"))
      (node (ref "C648") (pin "2") (pinfunction "2_2") (pintype "passive"))
      (node (ref "C649") (pin "2") (pinfunction "2_2") (pintype "passive"))
      (node (ref "C650") (pin "2") (pinfunction "2_2") (pintype "passive"))
      (node (ref "C651") (pin "2") (pinfunction "2_2") (pintype "passive"))
      (node (ref "C652") (pin "2") (pinfunction "2_2") (pintype "passive"))
      (node (ref "C653") (pin "2") (pinfunction "2_2") (pintype "passive"))
      (node (ref "C654") (pin "2") (pinfunction "2_2") (pintype "passive"))
      (node (ref "C655") (pin "2") (pinfunction "2_2") (pintype "passive"))
      (node (ref "C656") (pin "2") (pinfunction "2_2") (pintype "passive"))
      (node (ref "C657") (pin "2") (pinfunction "2_2") (pintype "passive"))
      (node (ref "C658") (pin "2") (pinfunction "2_2") (pintype "passive"))
      (node (ref "C659") (pin "2") (pinfunction "2_2") (pintype "passive"))
      (node (ref "C660") (pin "2") (pinfunction "2_2") (pintype "passive"))
    )
    (net (code "4") (name "P1V8") (class "Default")
      (node (ref "C636") (pin "2") (pinfunction "2_2") (pintype "passive"))
      (node (ref "C637") (pin "2") (pinfunction "2_2") (pintype "passive"))
      (node (ref "C638") (pin "2") (pinfunction "2_2") (pintype "passive"))
      (node (ref "C639") (pin "2") (pinfunction "2_2") (pintype "passive"))
      (node (ref "C640") (pin "2") (pinfunction "2_2") (pintype "passive"))
      (node (ref "C641") (pin "2") (pinfunction "2_2") (pintype "passive"))
      (node (ref "C661") (pin "2") (pinfunction "2_2") (pintype "passive"))
      (node (ref "C662") (pin "2") (pinfunction "2_2") (pintype "passive"))
      (node (ref "C663") (pin "2") (pinfunction "2_2") (pintype "passive"))
      (node (ref "C665") (pin "2") (pinfunction "2_2") (pintype "passive"))
      (node (ref "C666") (pin "2") (pinfunction "2_2") (pintype "passive"))
      (node (ref "C667") (pin "2") (pinfunction "2_2") (pintype "passive"))
      (node (ref "C840") (pin "2") (pinfunction "2_2") (pintype "passive"))
      (node (ref "C867") (pin "2") (pinfunction "2_2") (pintype "passive"))
      (node (ref "C868") (pin "2") (pinfunction "2_2") (pintype "passive"))
    )
    (net (code "5") (name "P3V3") (class "Default")
      (node (ref "C642") (pin "2") (pinfunction "2_2") (pintype "passive"))
      (node (ref "C643") (pin "2") (pinfunction "2_2") (pintype "passive"))
      (node (ref "C644") (pin "2") (pinfunction "2_2") (pintype "passive"))
      (node (ref "C664") (pin "2") (pinfunction "2_2") (pintype "passive"))
      (node (ref "C668") (pin "2") (pinfunction "2_2") (pintype "passive"))
    )
    (net (code "6") (name "VCCINT") (class "Default")
      (node (ref "C108") (pin "2") (pinfunction "2_2") (pintype "passive"))
      (node (ref "C119") (pin "2") (pinfunction "2_2") (pintype "passive"))
      (node (ref "C522") (pin "2") (pinfunction "2_2") (pintype "passive"))
      (node (ref "C523") (pin "2") (pinfunction "2_2") (pintype "passive"))
      (node (ref "C524") (pin "2") (pinfunction "2_2") (pintype "passive"))
      (node (ref "C525") (pin "2") (pinfunction "2_2") (pintype "passive"))
      (node (ref "C526") (pin "2") (pinfunction "2_2") (pintype "passive"))
      (node (ref "C527") (pin "2") (pinfunction "2_2") (pintype "passive"))
      (node (ref "C528") (pin "2") (pinfunction "2_2") (pintype "passive"))
      (node (ref "C529") (pin "2") (pinfunction "2_2") (pintype "passive"))
      (node (ref "C530") (pin "1") (pinfunction "1_1") (pintype "passive"))
      (node (ref "C531") (pin "1") (pinfunction "1_1") (pintype "passive"))
      (node (ref "C532") (pin "1") (pinfunction "1_1") (pintype "passive"))
    )
    (net (code "7") (name "VCCINT_IO_BRAM_PS_SDFEC") (class "Default")
      (node (ref "C533") (pin "2") (pinfunction "2_2") (pintype "passive"))
      (node (ref "C534") (pin "2") (pinfunction "2_2") (pintype "passive"))
      (node (ref "C535") (pin "2") (pinfunction "2_2") (pintype "passive"))
      (node (ref "C536") (pin "2") (pinfunction "2_2") (pintype "passive"))
      (node (ref "C537") (pin "2") (pinfunction "2_2") (pintype "passive"))
      (node (ref "C538") (pin "2") (pinfunction "2_2") (pintype "passive"))
      (node (ref "C539") (pin "2") (pinfunction "2_2") (pintype "passive"))
      (node (ref "C540") (pin "2") (pinfunction "2_2") (pintype "passive"))
      (node (ref "C541") (pin "2") (pinfunction "2_2") (pintype "passive"))
      (node (ref "C542") (pin "2") (pinfunction "2_2") (pintype "passive"))
      (node (ref "C543") (pin "2") (pinfunction "2_2") (pintype "passive"))
      (node (ref "C544") (pin "2") (pinfunction "2_2") (pintype "passive"))
      (node (ref "C545") (pin "2") (pinfunction "2_2") (pintype "passive"))
      (node (ref "C546") (pin "2") (pinfunction "2_2") (pintype "passive"))
      (node (ref "C547") (pin "2") (pinfunction "2_2") (pintype "passive"))
      (node (ref "C613") (pin "2") (pinfunction "2_2") (pintype "passive"))
      (node (ref "C614") (pin "2") (pinfunction "2_2") (pintype "passive"))
      (node (ref "C615") (pin "2") (pinfunction "2_2") (pintype "passive"))
      (node (ref "C616") (pin "2") (pinfunction "2_2") (pintype "passive"))
      (node (ref "C617") (pin "2") (pinfunction "2_2") (pintype "passive"))
      (node (ref "C618") (pin "2") (pinfunction "2_2") (pintype "passive"))
      (node (ref "C619") (pin "2") (pinfunction "2_2") (pintype "passive"))
      (node (ref "C620") (pin "2") (pinfunction "2_2") (pintype "passive"))
      (node (ref "C621") (pin "2") (pinfunction "2_2") (pintype "passive"))
      (node (ref "C622") (pin "2") (pinfunction "2_2") (pintype "passive"))
      (node (ref "C623") (pin "2") (pinfunction "2_2") (pintype "passive"))
      (node (ref "C624") (pin "2") (pinfunction "2_2") (pintype "passive"))
      (node (ref "C625") (pin "2") (pinfunction "2_2") (pintype "passive"))
      (node (ref "C626") (pin "2") (pinfunction "2_2") (pintype "passive"))
      (node (ref "C627") (pin "2") (pinfunction "2_2") (pintype "passive"))
      (node (ref "C628") (pin "2") (pinfunction "2_2") (pintype "passive"))
      (node (ref "C629") (pin "2") (pinfunction "2_2") (pintype "passive"))
      (node (ref "C630") (pin "2") (pinfunction "2_2") (pintype "passive"))
      (node (ref "C631") (pin "2") (pinfunction "2_2") (pintype "passive"))
      (node (ref "C632") (pin "2") (pinfunction "2_2") (pintype "passive"))
      (node (ref "C633") (pin "2") (pinfunction "2_2") (pintype "passive"))
      (node (ref "C634") (pin "2") (pinfunction "2_2") (pintype "passive"))
      (node (ref "C635") (pin "1") (pinfunction "1_1") (pintype "passive"))
    )
  )
)
